# schematic.net
KiCad netlist of a schematic drawn in EAGLE
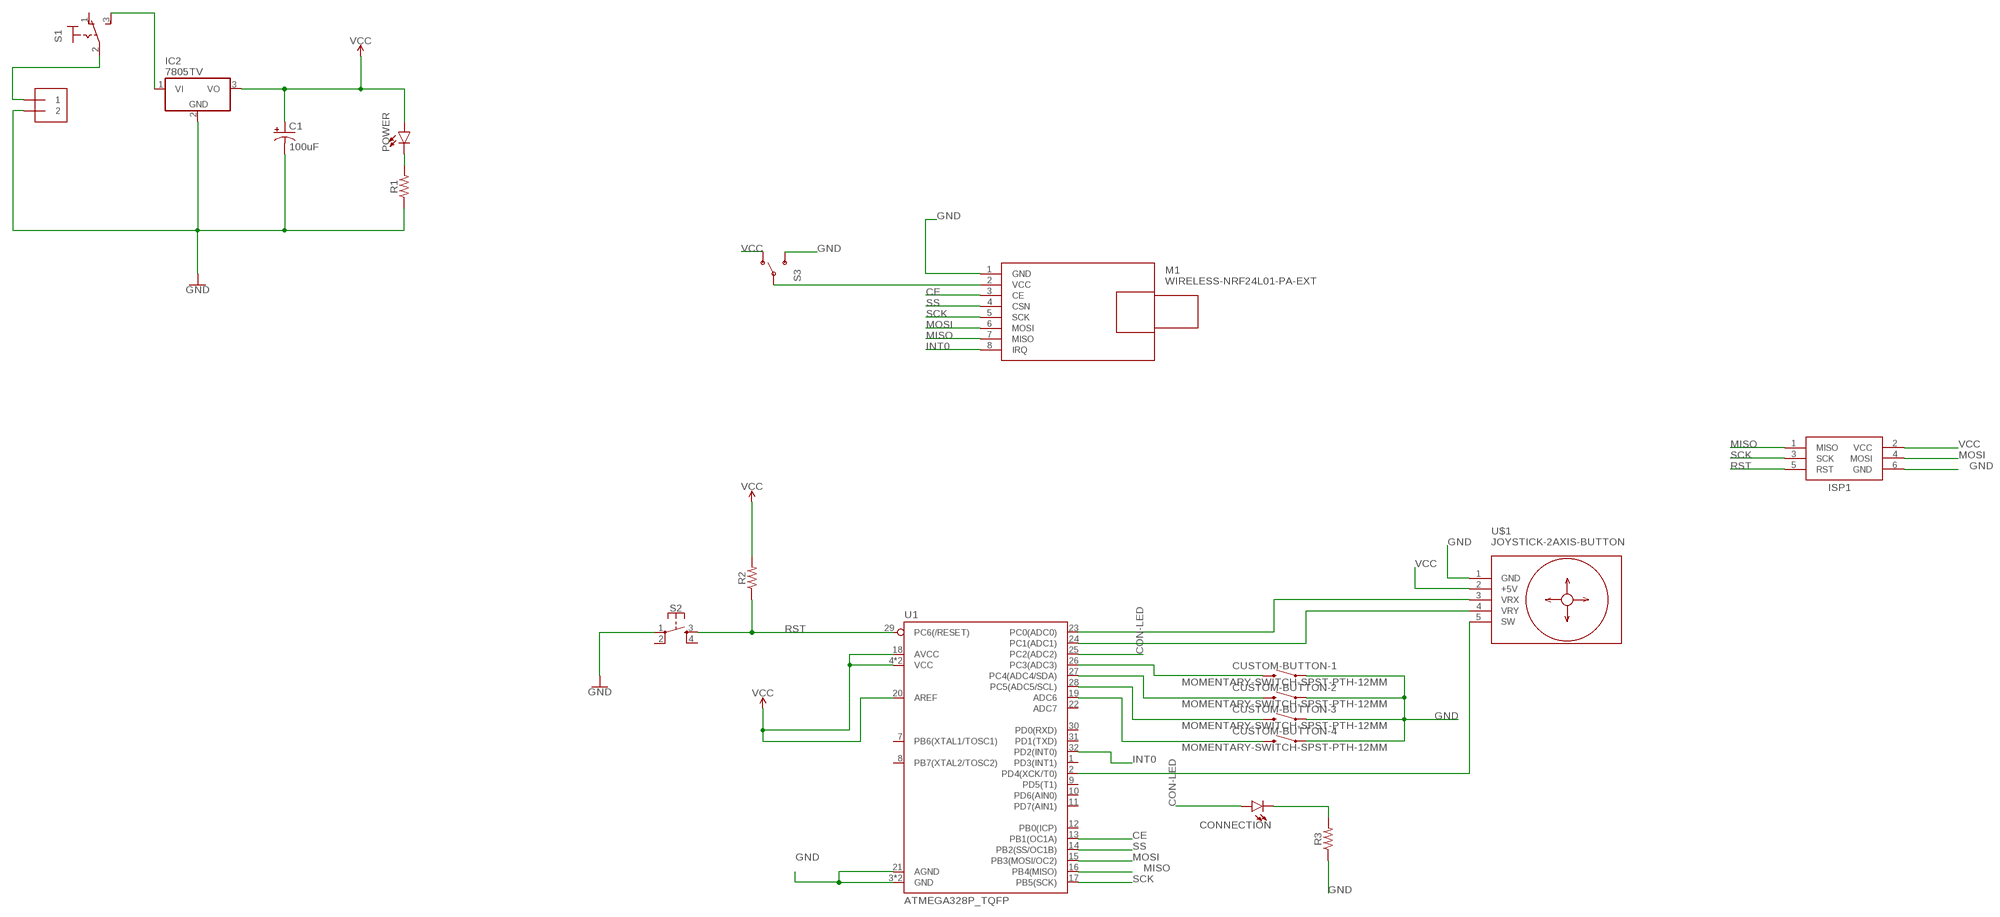
[diagram p0: schematic, sheet 1]

(export (version "E")
  (design (tool "Eeschema 10.0.6"))
  (components
    (comp (ref "C1")
      (value "100uF")
      (footprint "eagle-import:CPOL-RADIAL-2.5MM-6.5MM")
      (libsource (lib "eagle-import") (part "100UF-POLAR-RADIAL-2.5MM-25V-20%"))
    )
    (comp (ref "CONNECTION")
      (value "LED3MM")
      (footprint "eagle-import:LED_3MM")
      (libsource (lib "eagle-import") (part "LED3MM"))
    )
    (comp (ref "CUSTOM-BUTTON-1")
      (value "MOMENTARY-SWITCH-SPST-PTH-12MM")
      (footprint "eagle-import:TACTILE_SWITCH_PTH_12MM")
      (libsource (lib "eagle-import") (part "MOMENTARY-SWITCH-SPST-PTH-12MM"))
    )
    (comp (ref "CUSTOM-BUTTON-2")
      (value "MOMENTARY-SWITCH-SPST-PTH-12MM")
      (footprint "eagle-import:TACTILE_SWITCH_PTH_12MM")
      (libsource (lib "eagle-import") (part "MOMENTARY-SWITCH-SPST-PTH-12MM"))
    )
    (comp (ref "CUSTOM-BUTTON-3")
      (value "MOMENTARY-SWITCH-SPST-PTH-12MM")
      (footprint "eagle-import:TACTILE_SWITCH_PTH_12MM")
      (libsource (lib "eagle-import") (part "MOMENTARY-SWITCH-SPST-PTH-12MM"))
    )
    (comp (ref "CUSTOM-BUTTON-4")
      (value "MOMENTARY-SWITCH-SPST-PTH-12MM")
      (footprint "eagle-import:TACTILE_SWITCH_PTH_12MM")
      (libsource (lib "eagle-import") (part "MOMENTARY-SWITCH-SPST-PTH-12MM"))
    )
    (comp (ref "IC2")
      (value "7805TV")
      (footprint "eagle-import:TO220V")
      (libsource (lib "eagle-import") (part "78TV05"))
    )
    (comp (ref "ISP1")
      (value "AVRISP-6")
      (footprint "eagle-import:AVRISP")
      (libsource (lib "eagle-import") (part "AVRISP-6"))
    )
    (comp (ref "J1")
      (value "1X2-3.5MM")
      (footprint "eagle-import:1X2-3.5MM")
      (fields (field (name "SPICEPREFIX") "B"))
      (libsource (lib "eagle-import") (part "1X2-3.5MM"))
    )
    (comp (ref "M1")
      (value "WIRELESS-NRF24L01-PA-EXT")
      (footprint "eagle-import:WIRELESS-NRF24L01-PA-EXT")
      (libsource (lib "eagle-import") (part "WIRELESS-NRF24L01-PA-EXT"))
    )
    (comp (ref "POWER")
      (value "LED3MM")
      (footprint "eagle-import:LED_3MM")
      (libsource (lib "eagle-import") (part "LED3MM"))
    )
    (comp (ref "R1")
      (value "RESISTOR1206")
      (footprint "eagle-import:1206")
      (libsource (lib "eagle-import") (part "RESISTOR1206"))
    )
    (comp (ref "R2")
      (value "RESISTOR1206")
      (footprint "eagle-import:1206")
      (libsource (lib "eagle-import") (part "RESISTOR1206"))
    )
    (comp (ref "R3")
      (value "RESISTOR1206")
      (footprint "eagle-import:1206")
      (libsource (lib "eagle-import") (part "RESISTOR1206"))
    )
    (comp (ref "S1")
      (value "320-916")
      (footprint "eagle-import:320-916")
      (libsource (lib "eagle-import") (part "320-916"))
    )
    (comp (ref "S2")
      (value "MOMENTARY-SWITCH-SPST-2-SMD-4.6X2.8MM")
      (footprint "eagle-import:TACTILE_SWITCH_SMD_4.6X2.8MM")
      (libsource (lib "eagle-import") (part "MOMENTARY-SWITCH-SPST-2-SMD-4.6X2.8MM"))
    )
    (comp (ref "S3")
      (value "SWITCH-SPDTSMD")
      (footprint "eagle-import:SWITCH_SPDT_SMD")
      (libsource (lib "eagle-import") (part "SWITCH-SPDTSMD"))
    )
    (comp (ref "U$1")
      (value "JOYSTICK-2AXIS-BUTTON")
      (footprint "eagle-import:JOYSTICK-2AXIS-BUTTON")
      (libsource (lib "eagle-import") (part "JOYSTICK-2AXIS-BUTTON"))
    )
    (comp (ref "U1")
      (value "ATMEGA328P_TQFP")
      (footprint "eagle-import:TQFP32-08")
      (libsource (lib "eagle-import") (part "ATMEGA328P_TQFP"))
    )
  )
  (nets
    (net (code "1") (name "/CE") (class "Default")
      (node (ref "M1") (pin "3") (pinfunction "CE_3") (pintype "bidirectional"))
      (node (ref "U1") (pin "13") (pinfunction "PB1(OC1A)_13") (pintype "bidirectional"))
    )
    (net (code "2") (name "/CON-LED") (class "Default")
      (node (ref "CONNECTION") (pin "A") (pinfunction "A_A") (pintype "passive"))
      (node (ref "U1") (pin "25") (pinfunction "PC2(ADC2)_25") (pintype "bidirectional"))
    )
    (net (code "3") (name "/INT0") (class "Default")
      (node (ref "M1") (pin "8") (pinfunction "IRQ_8") (pintype "bidirectional"))
      (node (ref "U1") (pin "32") (pinfunction "PD2(INT0)_32") (pintype "bidirectional"))
    )
    (net (code "4") (name "/MISO") (class "Default")
      (node (ref "ISP1") (pin "1") (pinfunction "MISO_1") (pintype "input"))
      (node (ref "M1") (pin "7") (pinfunction "MISO_7") (pintype "bidirectional"))
      (node (ref "U1") (pin "16") (pinfunction "PB4(MISO)_16") (pintype "bidirectional"))
    )
    (net (code "5") (name "/MOSI") (class "Default")
      (node (ref "ISP1") (pin "4") (pinfunction "MOSI_4") (pintype "output"))
      (node (ref "M1") (pin "6") (pinfunction "MOSI_6") (pintype "bidirectional"))
      (node (ref "U1") (pin "15") (pinfunction "PB3(MOSI/OC2)_15") (pintype "bidirectional"))
    )
    (net (code "6") (name "/RST") (class "Default")
      (node (ref "ISP1") (pin "5") (pinfunction "RST_5") (pintype "output"))
      (node (ref "R2") (pin "1") (pinfunction "1_1") (pintype "passive"))
      (node (ref "S2") (pin "3") (pinfunction "3_3") (pintype "passive"))
      (node (ref "U1") (pin "29") (pinfunction "PC6(/RESET)_29") (pintype "bidirectional"))
    )
    (net (code "7") (name "/SCK") (class "Default")
      (node (ref "ISP1") (pin "3") (pinfunction "SCK_3") (pintype "output"))
      (node (ref "M1") (pin "5") (pinfunction "SCK_5") (pintype "bidirectional"))
      (node (ref "U1") (pin "17") (pinfunction "PB5(SCK)_17") (pintype "bidirectional"))
    )
    (net (code "8") (name "/SS") (class "Default")
      (node (ref "M1") (pin "4") (pinfunction "CSN_4") (pintype "bidirectional"))
      (node (ref "U1") (pin "14") (pinfunction "PB2(SS/OC1B)_14") (pintype "bidirectional"))
    )
    (net (code "9") (name "GND") (class "Default")
      (node (ref "C1") (pin "2") (pinfunction "-_2") (pintype "passive"))
      (node (ref "CUSTOM-BUTTON-1") (pin "1") (pinfunction "1_1") (pintype "passive"))
      (node (ref "CUSTOM-BUTTON-2") (pin "1") (pinfunction "1_1") (pintype "passive"))
      (node (ref "CUSTOM-BUTTON-3") (pin "1") (pinfunction "1_1") (pintype "passive"))
      (node (ref "CUSTOM-BUTTON-4") (pin "1") (pinfunction "1_1") (pintype "passive"))
      (node (ref "IC2") (pin "2") (pinfunction "GND_2") (pintype "passive"))
      (node (ref "ISP1") (pin "6") (pinfunction "GND_6") (pintype "power_in"))
      (node (ref "J1") (pin "2") (pinfunction "2_2") (pintype "passive"))
      (node (ref "M1") (pin "1") (pinfunction "GND_1") (pintype "power_in"))
      (node (ref "R1") (pin "1") (pinfunction "1_1") (pintype "passive"))
      (node (ref "R3") (pin "1") (pinfunction "1_1") (pintype "passive"))
      (node (ref "S2") (pin "1") (pinfunction "1_1") (pintype "passive"))
      (node (ref "S3") (pin "3") (pinfunction "S_3") (pintype "passive"))
      (node (ref "U$1") (pin "1") (pinfunction "GND_1") (pintype "power_in"))
      (node (ref "U1") (pin "21") (pinfunction "AGND_21") (pintype "bidirectional"))
      (node (ref "U1") (pin "3") (pinfunction "GND_3") (pintype "bidirectional"))
      (node (ref "U1") (pin "5") (pinfunction "GND_5") (pintype "bidirectional"))
    )
    (net (code "10") (name "Net-(CONNECTION-C)") (class "Default")
      (node (ref "CONNECTION") (pin "K") (pinfunction "C_K") (pintype "passive"))
      (node (ref "R3") (pin "2") (pinfunction "2_2") (pintype "passive"))
    )
    (net (code "11") (name "Net-(CUSTOM-BUTTON-1-2)") (class "Default")
      (node (ref "CUSTOM-BUTTON-1") (pin "3") (pinfunction "2_3") (pintype "passive"))
      (node (ref "U1") (pin "26") (pinfunction "PC3(ADC3)_26") (pintype "bidirectional"))
    )
    (net (code "12") (name "Net-(CUSTOM-BUTTON-2-2)") (class "Default")
      (node (ref "CUSTOM-BUTTON-2") (pin "3") (pinfunction "2_3") (pintype "passive"))
      (node (ref "U1") (pin "27") (pinfunction "PC4(ADC4/SDA)_27") (pintype "bidirectional"))
    )
    (net (code "13") (name "Net-(CUSTOM-BUTTON-3-2)") (class "Default")
      (node (ref "CUSTOM-BUTTON-3") (pin "3") (pinfunction "2_3") (pintype "passive"))
      (node (ref "U1") (pin "28") (pinfunction "PC5(ADC5/SCL)_28") (pintype "bidirectional"))
    )
    (net (code "14") (name "Net-(CUSTOM-BUTTON-4-2)") (class "Default")
      (node (ref "CUSTOM-BUTTON-4") (pin "3") (pinfunction "2_3") (pintype "passive"))
      (node (ref "U1") (pin "19") (pinfunction "ADC6_19") (pintype "bidirectional"))
    )
    (net (code "15") (name "Net-(IC2-VI)") (class "Default")
      (node (ref "IC2") (pin "1") (pinfunction "VI_1") (pintype "input"))
      (node (ref "S1") (pin "3") (pinfunction "S_3") (pintype "passive"))
    )
    (net (code "16") (name "Net-(M1-VCC)") (class "Default")
      (node (ref "M1") (pin "2") (pinfunction "VCC_2") (pintype "power_in"))
      (node (ref "S3") (pin "2") (pinfunction "P_2") (pintype "passive"))
    )
    (net (code "17") (name "Net-(POWER-C)") (class "Default")
      (node (ref "POWER") (pin "K") (pinfunction "C_K") (pintype "passive"))
      (node (ref "R1") (pin "2") (pinfunction "2_2") (pintype "passive"))
    )
    (net (code "18") (name "Net-(S1-P)") (class "Default")
      (node (ref "J1") (pin "1") (pinfunction "1_1") (pintype "passive"))
      (node (ref "S1") (pin "2") (pinfunction "P_2") (pintype "passive"))
    )
    (net (code "19") (name "Net-(U$1-SW)") (class "Default")
      (node (ref "U$1") (pin "5") (pinfunction "SW_5") (pintype "passive"))
      (node (ref "U1") (pin "2") (pinfunction "PD4(XCK/T0)_2") (pintype "bidirectional"))
    )
    (net (code "20") (name "Net-(U$1-VRX)") (class "Default")
      (node (ref "U$1") (pin "3") (pinfunction "VRX_3") (pintype "passive"))
      (node (ref "U1") (pin "23") (pinfunction "PC0(ADC0)_23") (pintype "bidirectional"))
    )
    (net (code "21") (name "Net-(U$1-VRY)") (class "Default")
      (node (ref "U$1") (pin "4") (pinfunction "VRY_4") (pintype "passive"))
      (node (ref "U1") (pin "24") (pinfunction "PC1(ADC1)_24") (pintype "bidirectional"))
    )
    (net (code "22") (name "VCC") (class "Default")
      (node (ref "C1") (pin "1") (pinfunction "+_1") (pintype "passive"))
      (node (ref "IC2") (pin "3") (pinfunction "VO_3") (pintype "passive"))
      (node (ref "ISP1") (pin "2") (pinfunction "VCC_2") (pintype "power_in"))
      (node (ref "POWER") (pin "A") (pinfunction "A_A") (pintype "passive"))
      (node (ref "R2") (pin "2") (pinfunction "2_2") (pintype "passive"))
      (node (ref "S3") (pin "1") (pinfunction "O_1") (pintype "passive"))
      (node (ref "U$1") (pin "2") (pinfunction "+5V_2") (pintype "power_in"))
      (node (ref "U1") (pin "18") (pinfunction "AVCC_18") (pintype "bidirectional"))
      (node (ref "U1") (pin "20") (pinfunction "AREF_20") (pintype "bidirectional"))
      (node (ref "U1") (pin "4") (pinfunction "VCC_4") (pintype "bidirectional"))
      (node (ref "U1") (pin "6") (pinfunction "VCC_6") (pintype "bidirectional"))
    )
    (net (code "23") (name "unconnected-(S1-O-Pad1)") (class "Default")
      (node (ref "S1") (pin "1") (pinfunction "O_1") (pintype "passive"))
    )
    (net (code "24") (name "unconnected-(S2-Pad2)") (class "Default")
      (node (ref "S2") (pin "2") (pinfunction "2_2") (pintype "passive"))
    )
    (net (code "25") (name "unconnected-(S2-Pad4)") (class "Default")
      (node (ref "S2") (pin "4") (pinfunction "4_4") (pintype "passive"))
    )
    (net (code "26") (name "unconnected-(U1-ADC7-Pad22)") (class "Default")
      (node (ref "U1") (pin "22") (pinfunction "ADC7_22") (pintype "bidirectional"))
    )
    (net (code "27") (name "unconnected-(U1-PB0(ICP)-Pad12)") (class "Default")
      (node (ref "U1") (pin "12") (pinfunction "PB0(ICP)_12") (pintype "bidirectional"))
    )
    (net (code "28") (name "unconnected-(U1-PB6(XTAL1{slash}TOSC1)-Pad7)") (class "Default")
      (node (ref "U1") (pin "7") (pinfunction "PB6(XTAL1/TOSC1)_7") (pintype "bidirectional"))
    )
    (net (code "29") (name "unconnected-(U1-PB7(XTAL2{slash}TOSC2)-Pad8)") (class "Default")
      (node (ref "U1") (pin "8") (pinfunction "PB7(XTAL2/TOSC2)_8") (pintype "bidirectional"))
    )
    (net (code "30") (name "unconnected-(U1-PD0(RXD)-Pad30)") (class "Default")
      (node (ref "U1") (pin "30") (pinfunction "PD0(RXD)_30") (pintype "bidirectional"))
    )
    (net (code "31") (name "unconnected-(U1-PD1(TXD)-Pad31)") (class "Default")
      (node (ref "U1") (pin "31") (pinfunction "PD1(TXD)_31") (pintype "bidirectional"))
    )
    (net (code "32") (name "unconnected-(U1-PD3(INT1)-Pad1)") (class "Default")
      (node (ref "U1") (pin "1") (pinfunction "PD3(INT1)_1") (pintype "bidirectional"))
    )
    (net (code "33") (name "unconnected-(U1-PD5(T1)-Pad9)") (class "Default")
      (node (ref "U1") (pin "9") (pinfunction "PD5(T1)_9") (pintype "bidirectional"))
    )
    (net (code "34") (name "unconnected-(U1-PD6(AIN0)-Pad10)") (class "Default")
      (node (ref "U1") (pin "10") (pinfunction "PD6(AIN0)_10") (pintype "bidirectional"))
    )
    (net (code "35") (name "unconnected-(U1-PD7(AIN1)-Pad11)") (class "Default")
      (node (ref "U1") (pin "11") (pinfunction "PD7(AIN1)_11") (pintype "bidirectional"))
    )
  )
)
